# main.net
KiCad netlist of a schematic drawn in Altium Designer
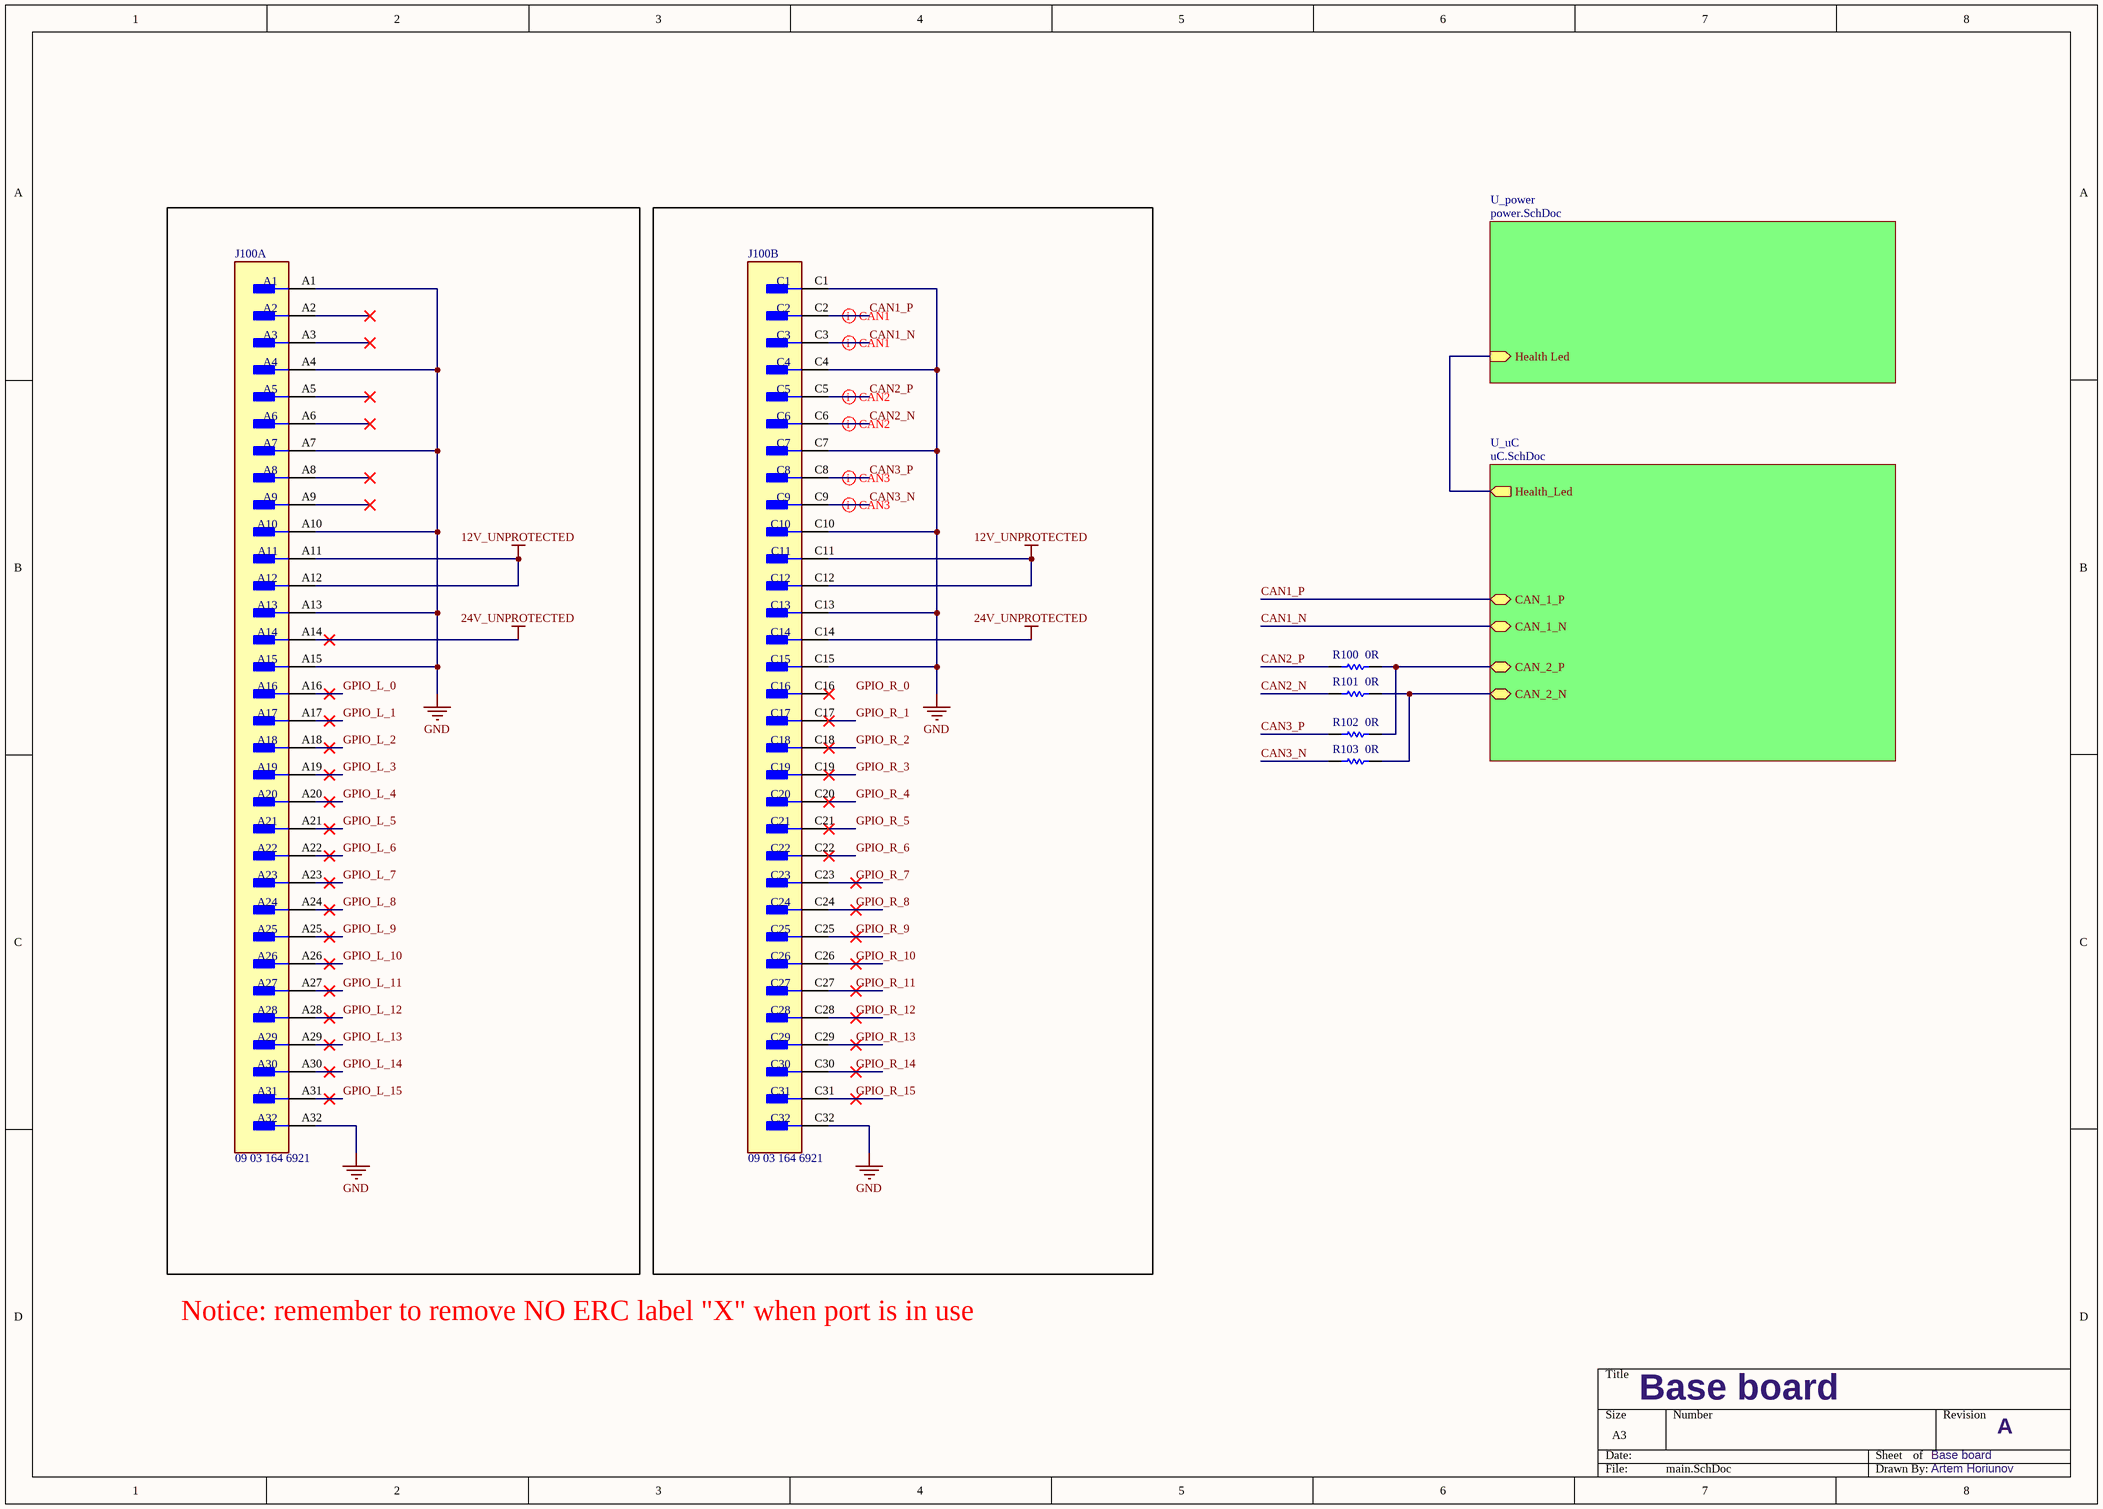
[diagram p0: main.SchDoc]

(export (version "E")
  (design (tool "Eeschema 10.0.6"))
  (components
    (comp (ref "J100")
      (value "09 03 164 6921")
      (footprint "FP-09_03_164_6921-MFG")
      (description "CONN DIN HDR 96POS PCB RA")
      (fields
        (field (name "MANUFACTURER") "Harting")
        (field (name "OCTOPART") "https://octopart.com/09031646921-harting+elektronik-42933")
      )
      (libsource (lib "Altium Content Vault") (part "242112e785ae82ea23b0e3c1eadb5b2"))
    )
    (comp (ref "R100")
      (value "0R")
      (footprint "RESC1608X55X25ML10T15")
      (description "Chip Resistor, 0 Ohm, +/- 5%, 0.1 W, -55 to 155 degC, 0603 (1608 Metric), RoHS, Tape and Reel")
      (fields (field (name "TOLERANCE") "5%") (field (name "MANUFACTURER") "Yageo"))
      (libsource (lib "Altium Content Vault") (part "RES-2"))
    )
    (comp (ref "R101")
      (value "0R")
      (footprint "RESC1608X55X25ML10T15")
      (description "Chip Resistor, 0 Ohm, +/- 5%, 0.1 W, -55 to 155 degC, 0603 (1608 Metric), RoHS, Tape and Reel")
      (fields (field (name "TOLERANCE") "5%") (field (name "MANUFACTURER") "Yageo"))
      (libsource (lib "Altium Content Vault") (part "RES-2"))
    )
    (comp (ref "R102")
      (value "0R")
      (footprint "RESC1608X55X25ML10T15")
      (description "Chip Resistor, 0 Ohm, +/- 5%, 0.1 W, -55 to 155 degC, 0603 (1608 Metric), RoHS, Tape and Reel")
      (fields (field (name "TOLERANCE") "5%") (field (name "MANUFACTURER") "Yageo"))
      (libsource (lib "Altium Content Vault") (part "RES-2"))
    )
    (comp (ref "R103")
      (value "0R")
      (footprint "RESC1608X55X25ML10T15")
      (description "Chip Resistor, 0 Ohm, +/- 5%, 0.1 W, -55 to 155 degC, 0603 (1608 Metric), RoHS, Tape and Reel")
      (fields (field (name "TOLERANCE") "5%") (field (name "MANUFACTURER") "Yageo"))
      (libsource (lib "Altium Content Vault") (part "RES-2"))
    )
  )
  (nets
    (net (code "1") (name "/CAN1_N") (class "Default")
      (node (ref "J100") (pin "C3") (pinfunction "C3_C3") (pintype "passive"))
    )
    (net (code "2") (name "/CAN1_P") (class "Default")
      (node (ref "J100") (pin "C2") (pinfunction "C2_C2") (pintype "passive"))
    )
    (net (code "3") (name "/CAN2_N") (class "Default")
      (node (ref "J100") (pin "C6") (pinfunction "C6_C6") (pintype "passive"))
      (node (ref "R101") (pin "1") (pinfunction "1_1") (pintype "passive"))
    )
    (net (code "4") (name "/CAN2_P") (class "Default")
      (node (ref "J100") (pin "C5") (pinfunction "C5_C5") (pintype "passive"))
      (node (ref "R100") (pin "1") (pinfunction "1_1") (pintype "passive"))
    )
    (net (code "5") (name "/CAN3_N") (class "Default")
      (node (ref "J100") (pin "C9") (pinfunction "C9_C9") (pintype "passive"))
      (node (ref "R103") (pin "1") (pinfunction "1_1") (pintype "passive"))
    )
    (net (code "6") (name "/CAN3_P") (class "Default")
      (node (ref "J100") (pin "C8") (pinfunction "C8_C8") (pintype "passive"))
      (node (ref "R102") (pin "1") (pinfunction "1_1") (pintype "passive"))
    )
    (net (code "7") (name "/CAN_2_N") (class "Default")
      (node (ref "R101") (pin "2") (pinfunction "2_2") (pintype "passive"))
      (node (ref "R103") (pin "2") (pinfunction "2_2") (pintype "passive"))
    )
    (net (code "8") (name "/CAN_2_P") (class "Default")
      (node (ref "R100") (pin "2") (pinfunction "2_2") (pintype "passive"))
      (node (ref "R102") (pin "2") (pinfunction "2_2") (pintype "passive"))
    )
    (net (code "9") (name "/GPIO_L_0") (class "Default")
      (node (ref "J100") (pin "A16") (pinfunction "A16_A16") (pintype "passive"))
    )
    (net (code "10") (name "/GPIO_L_1") (class "Default")
      (node (ref "J100") (pin "A17") (pinfunction "A17_A17") (pintype "passive"))
    )
    (net (code "11") (name "/GPIO_L_2") (class "Default")
      (node (ref "J100") (pin "A18") (pinfunction "A18_A18") (pintype "passive"))
    )
    (net (code "12") (name "/GPIO_L_3") (class "Default")
      (node (ref "J100") (pin "A19") (pinfunction "A19_A19") (pintype "passive"))
    )
    (net (code "13") (name "/GPIO_L_4") (class "Default")
      (node (ref "J100") (pin "A20") (pinfunction "A20_A20") (pintype "passive"))
    )
    (net (code "14") (name "/GPIO_L_5") (class "Default")
      (node (ref "J100") (pin "A21") (pinfunction "A21_A21") (pintype "passive"))
    )
    (net (code "15") (name "/GPIO_L_6") (class "Default")
      (node (ref "J100") (pin "A22") (pinfunction "A22_A22") (pintype "passive"))
    )
    (net (code "16") (name "/GPIO_L_7") (class "Default")
      (node (ref "J100") (pin "A23") (pinfunction "A23_A23") (pintype "passive"))
    )
    (net (code "17") (name "/GPIO_L_8") (class "Default")
      (node (ref "J100") (pin "A24") (pinfunction "A24_A24") (pintype "passive"))
    )
    (net (code "18") (name "/GPIO_L_9") (class "Default")
      (node (ref "J100") (pin "A25") (pinfunction "A25_A25") (pintype "passive"))
    )
    (net (code "19") (name "/GPIO_L_10") (class "Default")
      (node (ref "J100") (pin "A26") (pinfunction "A26_A26") (pintype "passive"))
    )
    (net (code "20") (name "/GPIO_L_11") (class "Default")
      (node (ref "J100") (pin "A27") (pinfunction "A27_A27") (pintype "passive"))
    )
    (net (code "21") (name "/GPIO_L_12") (class "Default")
      (node (ref "J100") (pin "A28") (pinfunction "A28_A28") (pintype "passive"))
    )
    (net (code "22") (name "/GPIO_L_13") (class "Default")
      (node (ref "J100") (pin "A29") (pinfunction "A29_A29") (pintype "passive"))
    )
    (net (code "23") (name "/GPIO_L_14") (class "Default")
      (node (ref "J100") (pin "A30") (pinfunction "A30_A30") (pintype "passive"))
    )
    (net (code "24") (name "/GPIO_L_15") (class "Default")
      (node (ref "J100") (pin "A31") (pinfunction "A31_A31") (pintype "passive"))
    )
    (net (code "26") (name "/GPIO_R_1") (class "Default")
      (node (ref "J100") (pin "C17") (pinfunction "C17_C17") (pintype "passive+no_connect"))
    )
    (net (code "27") (name "/GPIO_R_2") (class "Default")
      (node (ref "J100") (pin "C18") (pinfunction "C18_C18") (pintype "passive+no_connect"))
    )
    (net (code "28") (name "/GPIO_R_3") (class "Default")
      (node (ref "J100") (pin "C19") (pinfunction "C19_C19") (pintype "passive+no_connect"))
    )
    (net (code "29") (name "/GPIO_R_4") (class "Default")
      (node (ref "J100") (pin "C20") (pinfunction "C20_C20") (pintype "passive+no_connect"))
    )
    (net (code "30") (name "/GPIO_R_5") (class "Default")
      (node (ref "J100") (pin "C21") (pinfunction "C21_C21") (pintype "passive+no_connect"))
    )
    (net (code "31") (name "/GPIO_R_6") (class "Default")
      (node (ref "J100") (pin "C22") (pinfunction "C22_C22") (pintype "passive+no_connect"))
    )
    (net (code "42") (name "/GPIO_R_7") (class "Default")
      (node (ref "J100") (pin "C23") (pinfunction "C23_C23") (pintype "passive"))
    )
    (net (code "43") (name "/GPIO_R_8") (class "Default")
      (node (ref "J100") (pin "C24") (pinfunction "C24_C24") (pintype "passive"))
    )
    (net (code "44") (name "/GPIO_R_9") (class "Default")
      (node (ref "J100") (pin "C25") (pinfunction "C25_C25") (pintype "passive"))
    )
    (net (code "45") (name "/GPIO_R_10") (class "Default")
      (node (ref "J100") (pin "C26") (pinfunction "C26_C26") (pintype "passive"))
    )
    (net (code "46") (name "/GPIO_R_11") (class "Default")
      (node (ref "J100") (pin "C27") (pinfunction "C27_C27") (pintype "passive"))
    )
    (net (code "47") (name "/GPIO_R_12") (class "Default")
      (node (ref "J100") (pin "C28") (pinfunction "C28_C28") (pintype "passive"))
    )
    (net (code "48") (name "/GPIO_R_13") (class "Default")
      (node (ref "J100") (pin "C29") (pinfunction "C29_C29") (pintype "passive"))
    )
    (net (code "49") (name "/GPIO_R_14") (class "Default")
      (node (ref "J100") (pin "C30") (pinfunction "C30_C30") (pintype "passive"))
    )
    (net (code "50") (name "/GPIO_R_15") (class "Default")
      (node (ref "J100") (pin "C31") (pinfunction "C31_C31") (pintype "passive"))
    )
    (net (code "51") (name "12V_UNPROTECTED") (class "Default")
      (node (ref "J100") (pin "A11") (pinfunction "A11_A11") (pintype "passive"))
      (node (ref "J100") (pin "A12") (pinfunction "A12_A12") (pintype "passive"))
      (node (ref "J100") (pin "C11") (pinfunction "C11_C11") (pintype "passive"))
      (node (ref "J100") (pin "C12") (pinfunction "C12_C12") (pintype "passive"))
    )
    (net (code "52") (name "24V_UNPROTECTED") (class "Default")
      (node (ref "J100") (pin "A14") (pinfunction "A14_A14") (pintype "passive"))
      (node (ref "J100") (pin "C14") (pinfunction "C14_C14") (pintype "passive"))
    )
    (net (code "53") (name "GND") (class "Default")
      (node (ref "J100") (pin "A1") (pinfunction "A1_A1") (pintype "passive"))
      (node (ref "J100") (pin "A10") (pinfunction "A10_A10") (pintype "passive"))
      (node (ref "J100") (pin "A13") (pinfunction "A13_A13") (pintype "passive"))
      (node (ref "J100") (pin "A15") (pinfunction "A15_A15") (pintype "passive"))
      (node (ref "J100") (pin "A32") (pinfunction "A32_A32") (pintype "passive"))
      (node (ref "J100") (pin "A4") (pinfunction "A4_A4") (pintype "passive"))
      (node (ref "J100") (pin "A7") (pinfunction "A7_A7") (pintype "passive"))
      (node (ref "J100") (pin "C1") (pinfunction "C1_C1") (pintype "passive"))
      (node (ref "J100") (pin "C10") (pinfunction "C10_C10") (pintype "passive"))
      (node (ref "J100") (pin "C13") (pinfunction "C13_C13") (pintype "passive"))
      (node (ref "J100") (pin "C15") (pinfunction "C15_C15") (pintype "passive"))
      (node (ref "J100") (pin "C32") (pinfunction "C32_C32") (pintype "passive"))
      (node (ref "J100") (pin "C4") (pinfunction "C4_C4") (pintype "passive"))
      (node (ref "J100") (pin "C7") (pinfunction "C7_C7") (pintype "passive"))
    )
    (net (code "54") (name "unconnected-(J100-PadA2)") (class "Default")
      (node (ref "J100") (pin "A2") (pinfunction "A2_A2") (pintype "passive+no_connect"))
    )
    (net (code "55") (name "unconnected-(J100-PadA3)") (class "Default")
      (node (ref "J100") (pin "A3") (pinfunction "A3_A3") (pintype "passive+no_connect"))
    )
    (net (code "56") (name "unconnected-(J100-PadA5)") (class "Default")
      (node (ref "J100") (pin "A5") (pinfunction "A5_A5") (pintype "passive+no_connect"))
    )
    (net (code "57") (name "unconnected-(J100-PadA6)") (class "Default")
      (node (ref "J100") (pin "A6") (pinfunction "A6_A6") (pintype "passive+no_connect"))
    )
    (net (code "58") (name "unconnected-(J100-PadA8)") (class "Default")
      (node (ref "J100") (pin "A8") (pinfunction "A8_A8") (pintype "passive+no_connect"))
    )
    (net (code "59") (name "unconnected-(J100-PadA9)") (class "Default")
      (node (ref "J100") (pin "A9") (pinfunction "A9_A9") (pintype "passive+no_connect"))
    )
    (net (code "60") (name "unconnected-(J100-PadC16)") (class "Default")
      (node (ref "J100") (pin "C16") (pinfunction "C16_C16") (pintype "passive+no_connect"))
    )
  )
)
